# fan_control.net
KiCad netlist of a schematic drawn in EAGLE
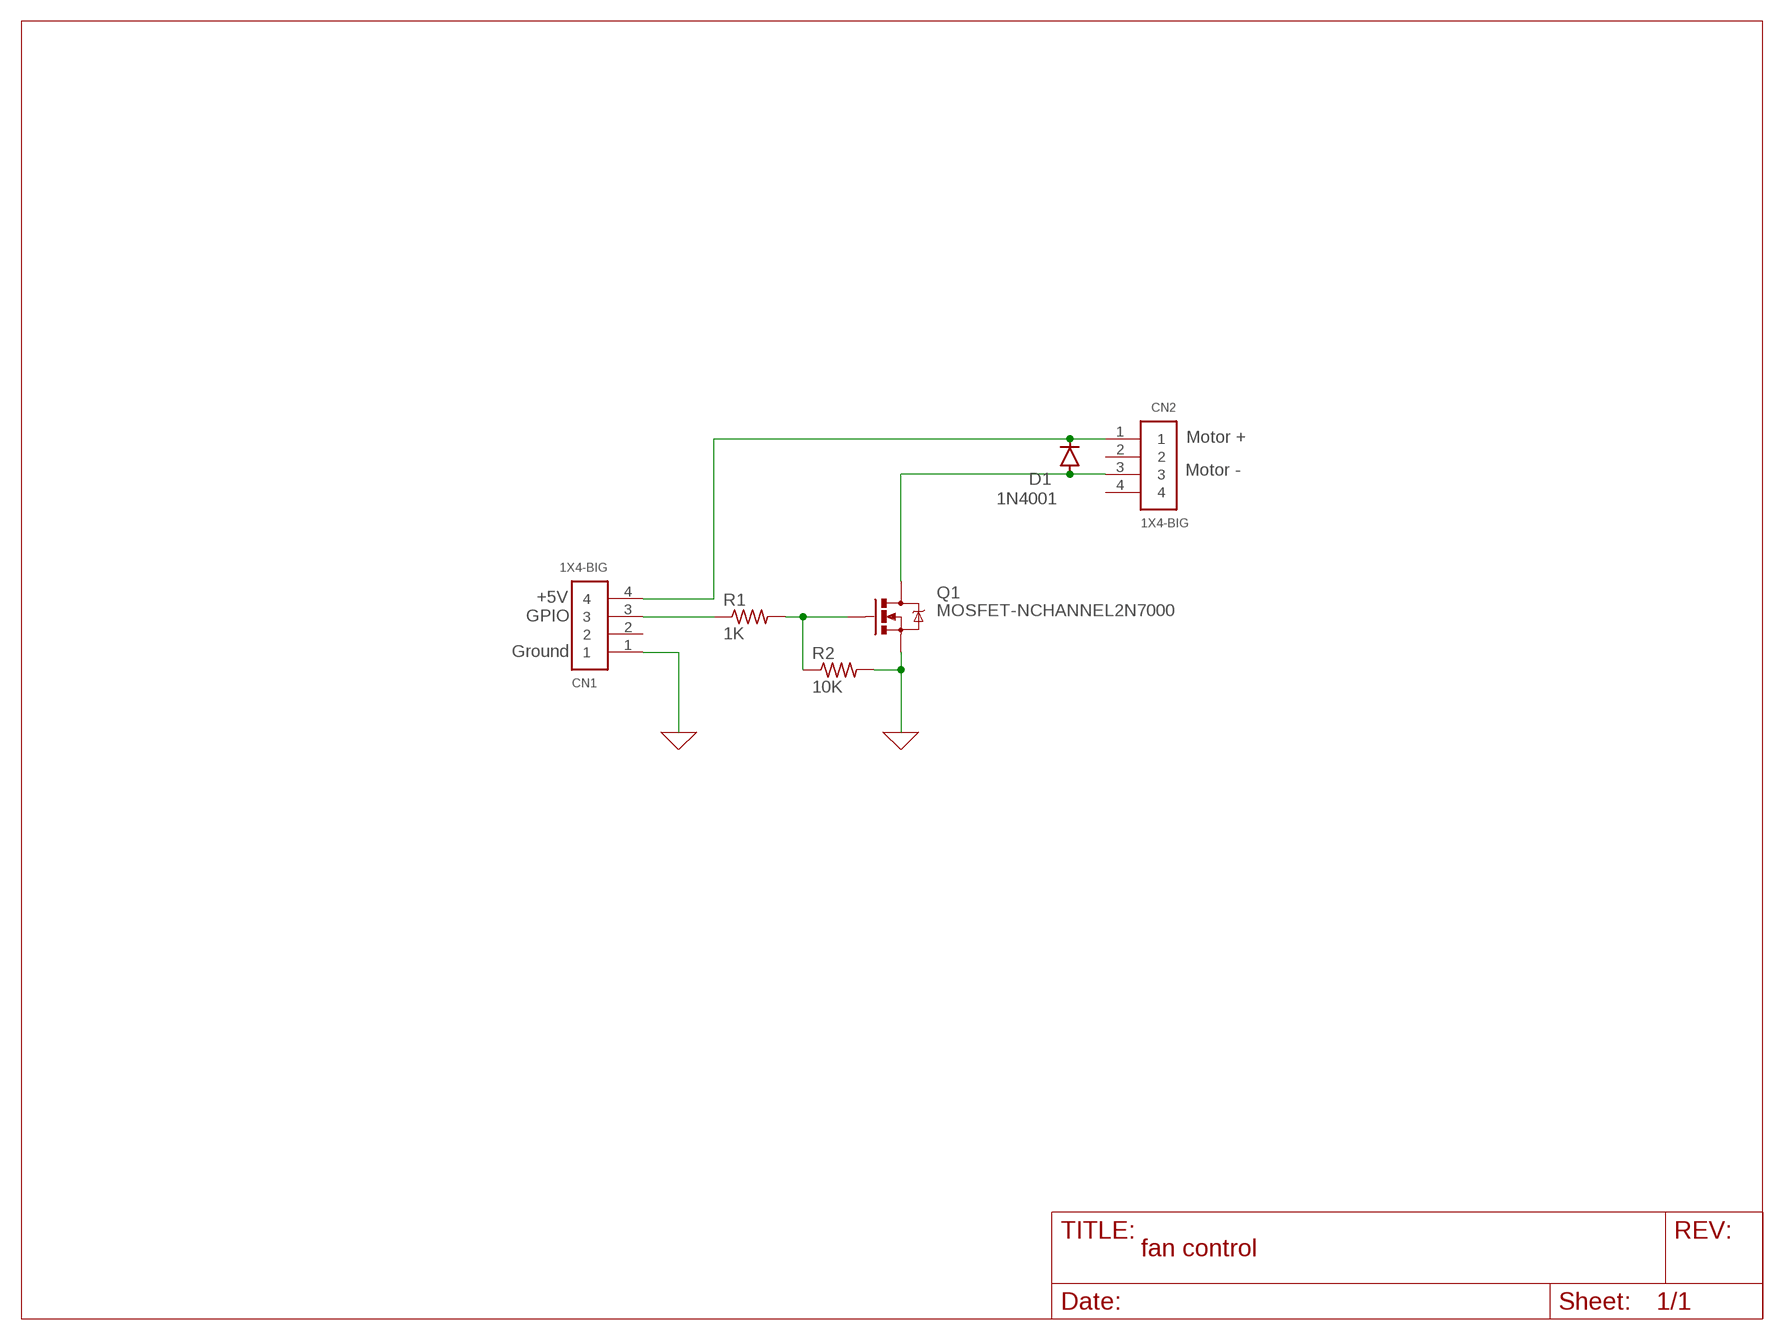
[diagram p0: schematic, sheet 1]

(export (version "E")
  (design (tool "Eeschema 10.0.6"))
  (components
    (comp (ref "CN1")
      (value "1X4-BIG")
      (footprint "eagle-import:1X04-BIG")
      (libsource (lib "eagle-import") (part "1X4-BIG"))
    )
    (comp (ref "CN2")
      (value "1X4-BIG")
      (footprint "eagle-import:1X04-BIG")
      (libsource (lib "eagle-import") (part "1X4-BIG"))
    )
    (comp (ref "D1")
      (value "1N4001")
      (footprint "eagle-import:DO-41")
      (fields
        (field (name "DIGIKEY_PART_NUMBER") "1N4004MSCT-ND")
        (field (name "MANUFACTURER") "Micro Commercial Co")
        (field (name "MPN") "1N4004")
        (field (name "CREATED_BY") "PCBLayout.com")
      )
      (libsource (lib "eagle-import") (part "1N4004"))
    )
    (comp (ref "Q1")
      (value "MOSFET-NCHANNEL2N7000")
      (footprint "eagle-import:TO-92")
      (libsource (lib "eagle-import") (part "MOSFET-NCHANNEL2N7000"))
    )
    (comp (ref "R1")
      (value "1K")
      (footprint "eagle-import:0207_10")
      (libsource (lib "eagle-import") (part "R-US_0207/10"))
    )
    (comp (ref "R2")
      (value "10K")
      (footprint "eagle-import:0207_10")
      (libsource (lib "eagle-import") (part "R-US_0207/10"))
    )
  )
  (nets
    (net (code "1") (name "GND") (class "Default")
      (node (ref "CN1") (pin "1") (pinfunction "1_1") (pintype "bidirectional"))
      (node (ref "Q1") (pin "1") (pinfunction "S_1") (pintype "passive"))
      (node (ref "R2") (pin "2") (pinfunction "2_2") (pintype "passive"))
    )
    (net (code "2") (name "Net-(CN1-Pad3)") (class "Default")
      (node (ref "CN1") (pin "3") (pinfunction "3_3") (pintype "bidirectional"))
      (node (ref "R1") (pin "1") (pinfunction "1_1") (pintype "passive"))
    )
    (net (code "3") (name "Net-(CN1-Pad4)") (class "Default")
      (node (ref "CN1") (pin "4") (pinfunction "4_4") (pintype "bidirectional"))
      (node (ref "CN2") (pin "1") (pinfunction "1_1") (pintype "bidirectional"))
      (node (ref "D1") (pin "C") (pinfunction "C_C") (pintype "passive"))
    )
    (net (code "4") (name "Net-(Q1-D)") (class "Default")
      (node (ref "CN2") (pin "3") (pinfunction "3_3") (pintype "bidirectional"))
      (node (ref "D1") (pin "A") (pinfunction "A_A") (pintype "passive"))
      (node (ref "Q1") (pin "3") (pinfunction "D_3") (pintype "passive"))
    )
    (net (code "5") (name "Net-(Q1-G)") (class "Default")
      (node (ref "Q1") (pin "2") (pinfunction "G_2") (pintype "passive"))
      (node (ref "R1") (pin "2") (pinfunction "2_2") (pintype "passive"))
      (node (ref "R2") (pin "1") (pinfunction "1_1") (pintype "passive"))
    )
    (net (code "6") (name "unconnected-(CN1-Pad2)") (class "Default")
      (node (ref "CN1") (pin "2") (pinfunction "2_2") (pintype "bidirectional"))
    )
    (net (code "7") (name "unconnected-(CN2-Pad2)") (class "Default")
      (node (ref "CN2") (pin "2") (pinfunction "2_2") (pintype "bidirectional"))
    )
    (net (code "8") (name "unconnected-(CN2-Pad4)") (class "Default")
      (node (ref "CN2") (pin "4") (pinfunction "4_4") (pintype "bidirectional"))
    )
  )
)
